# Sheet1.net
KiCad netlist of a schematic drawn in Altium Designer
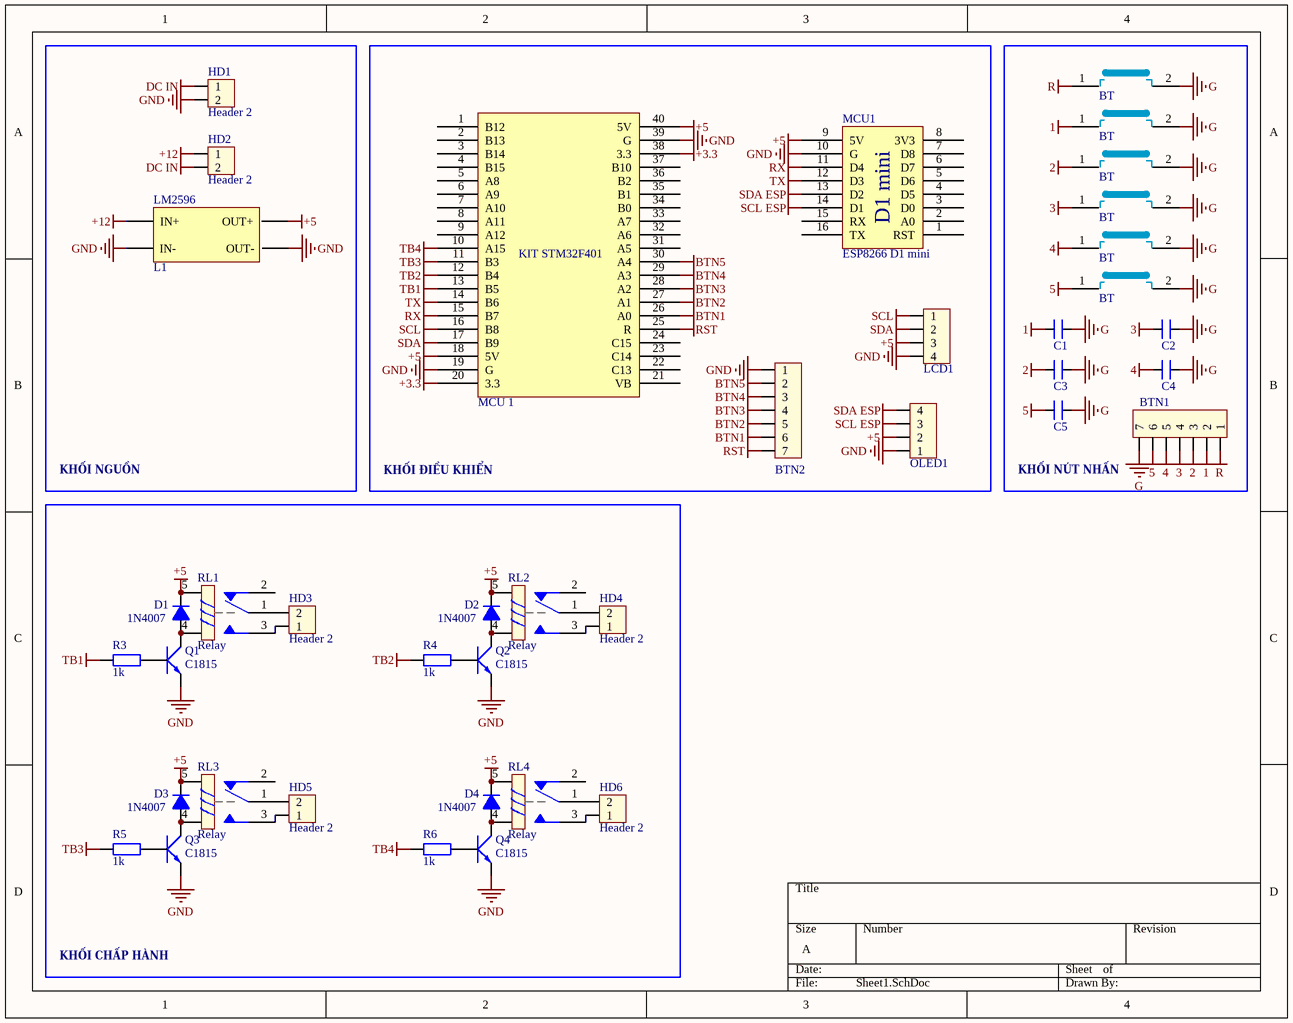
[diagram p0: Sheet1.SchDoc]

(export (version "E")
  (design (tool "Eeschema 10.0.6"))
  (components
    (comp (ref "BT1") (value "BT") (footprint "SW4") (libsource (lib "MY_LIBRARY") (part "BUTTON")))
    (comp (ref "BT2") (value "BT") (footprint "SW4") (libsource (lib "MY_LIBRARY") (part "BUTTON")))
    (comp (ref "BT3") (value "BT") (footprint "SW4") (libsource (lib "MY_LIBRARY") (part "BUTTON")))
    (comp (ref "BT4") (value "BT") (footprint "SW4") (libsource (lib "MY_LIBRARY") (part "BUTTON")))
    (comp (ref "BT5") (value "BT") (footprint "SW4") (libsource (lib "MY_LIBRARY") (part "BUTTON")))
    (comp (ref "BT6") (value "BT") (footprint "SW4") (libsource (lib "MY_LIBRARY") (part "BUTTON")))
    (comp (ref "BTN1")
      (value "JP7")
      (footprint "CON7")
      (description "Connector 7")
      (libsource (lib "MY_LIBRARY") (part "Con7"))
    )
    (comp (ref "BTN2")
      (value "JP7")
      (footprint "CON7")
      (description "Connector 7")
      (libsource (lib "MY_LIBRARY") (part "Con7"))
    )
    (comp (ref "C1") (value "CAP gom") (footprint "CN1") (libsource (lib "MY_LIBRARY") (part "CAP gom")))
    (comp (ref "C2") (value "CAP gom") (footprint "CN1") (libsource (lib "MY_LIBRARY") (part "CAP gom")))
    (comp (ref "C3") (value "CAP gom") (footprint "CN1") (libsource (lib "MY_LIBRARY") (part "CAP gom")))
    (comp (ref "C4") (value "CAP gom") (footprint "CN1") (libsource (lib "MY_LIBRARY") (part "CAP gom")))
    (comp (ref "C5") (value "CAP gom") (footprint "CN1") (libsource (lib "MY_LIBRARY") (part "CAP gom")))
    (comp (ref "D1")
      (value "1N4007")
      (footprint "D2A")
      (description "Diode 1A")
      (libsource (lib "Thuvien3D") (part "D1A"))
    )
    (comp (ref "D2")
      (value "1N4007")
      (footprint "D2A")
      (description "Diode 1A")
      (libsource (lib "Thuvien3D") (part "D1A"))
    )
    (comp (ref "D3")
      (value "1N4007")
      (footprint "D2A")
      (description "Diode 1A")
      (libsource (lib "Thuvien3D") (part "D1A"))
    )
    (comp (ref "D4")
      (value "1N4007")
      (footprint "D2A")
      (description "Diode 1A")
      (libsource (lib "Thuvien3D") (part "D1A"))
    )
    (comp (ref "HD1")
      (value "Header 2")
      (footprint "HED2")
      (description "Header 2 (Green)")
      (libsource (lib "Thuvien3D") (part "Hed2"))
    )
    (comp (ref "HD2")
      (value "Header 2")
      (footprint "HED2")
      (description "Header 2 (Green)")
      (libsource (lib "Thuvien3D") (part "Hed2"))
    )
    (comp (ref "HD3")
      (value "Header 2")
      (footprint "HED2")
      (description "Header 2 (Green)")
      (libsource (lib "") (part "Hed2_1"))
    )
    (comp (ref "HD4")
      (value "Header 2")
      (footprint "HED2")
      (description "Header 2 (Green)")
      (libsource (lib "") (part "Hed2_1"))
    )
    (comp (ref "HD5")
      (value "Header 2")
      (footprint "HED2")
      (description "Header 2 (Green)")
      (libsource (lib "") (part "Hed2_1"))
    )
    (comp (ref "HD6")
      (value "Header 2")
      (footprint "HED2")
      (description "Header 2 (Green)")
      (libsource (lib "") (part "Hed2_1"))
    )
    (comp (ref "L1")
      (value "BUCK_LM2596")
      (footprint "BUCK_LM2596")
      (libsource (lib "MY_LIBRARY") (part "BUCK_LM2596"))
    )
    (comp (ref "LCD1")
      (value "JP4")
      (footprint "CON4")
      (description "Connector 4")
      (libsource (lib "") (part "Con4_1"))
    )
    (comp (ref "MCU 1")
      (value "KIT STM32F401")
      (footprint "KIT STM32F401")
      (libsource (lib "MY_LIBRARY") (part "KIT STM32F401"))
    )
    (comp (ref "MCU1")
      (value "ESP8266 D1 mini")
      (footprint "ESP D1 mini")
      (libsource (lib "MY_LIBRARY") (part "ESP8266 D1 mini"))
    )
    (comp (ref "OLED1")
      (value "JP4")
      (footprint "CON4")
      (description "Connector 4")
      (libsource (lib "MY_LIBRARY") (part "Con4"))
    )
    (comp (ref "Q1")
      (value "C1815")
      (footprint "QTO-92")
      (description "NPN 600mW, ECB")
      (libsource (lib "Thuvien3D") (part "C1815"))
    )
    (comp (ref "Q2")
      (value "C1815")
      (footprint "QTO-92")
      (description "NPN 600mW, ECB")
      (libsource (lib "Thuvien3D") (part "C1815"))
    )
    (comp (ref "Q3")
      (value "C1815")
      (footprint "QTO-92")
      (description "NPN 600mW, ECB")
      (libsource (lib "Thuvien3D") (part "C1815"))
    )
    (comp (ref "Q4")
      (value "C1815")
      (footprint "QTO-92")
      (description "NPN 600mW, ECB")
      (libsource (lib "Thuvien3D") (part "C1815"))
    )
    (comp (ref "R3")
      (value "1k")
      (footprint "R1/2W")
      (description "Resistor 1/4W")
      (libsource (lib "Thuvien3D") (part "R1/4W"))
    )
    (comp (ref "R4")
      (value "1k")
      (footprint "R1/2W")
      (description "Resistor 1/4W")
      (libsource (lib "Thuvien3D") (part "R1/4W"))
    )
    (comp (ref "R5")
      (value "1k")
      (footprint "R1/2W")
      (description "Resistor 1/4W")
      (libsource (lib "Thuvien3D") (part "R1/4W"))
    )
    (comp (ref "R6")
      (value "1k")
      (footprint "R1/2W")
      (description "Resistor 1/4W")
      (libsource (lib "Thuvien3D") (part "R1/4W"))
    )
    (comp (ref "RL1")
      (value "Relay")
      (footprint "RL_SPDT_10A")
      (description "Relay SPDT 5 Pin")
      (libsource (lib "MY_LIBRARY") (part "Relay SRD"))
    )
    (comp (ref "RL2")
      (value "Relay")
      (footprint "RL_SPDT_10A")
      (description "Relay SPDT 5 Pin")
      (libsource (lib "MY_LIBRARY") (part "Relay SRD"))
    )
    (comp (ref "RL3")
      (value "Relay")
      (footprint "RL_SPDT_10A")
      (description "Relay SPDT 5 Pin")
      (libsource (lib "MY_LIBRARY") (part "Relay SRD"))
    )
    (comp (ref "RL4")
      (value "Relay")
      (footprint "RL_SPDT_10A")
      (description "Relay SPDT 5 Pin")
      (libsource (lib "MY_LIBRARY") (part "Relay SRD"))
    )
  )
  (nets
    (net (code "1") (name "+3.3") (class "Default")
      (node (ref "MCU 1") (pin "20") (pinfunction "3.3_20") (pintype "passive"))
      (node (ref "MCU 1") (pin "38") (pinfunction "3.3_38") (pintype "passive"))
    )
    (net (code "2") (name "+5") (class "Default")
      (node (ref "D1") (pin "2") (pinfunction "K_2") (pintype "passive"))
      (node (ref "D2") (pin "2") (pinfunction "K_2") (pintype "passive"))
      (node (ref "D3") (pin "2") (pinfunction "K_2") (pintype "passive"))
      (node (ref "D4") (pin "2") (pinfunction "K_2") (pintype "passive"))
      (node (ref "L1") (pin "4") (pinfunction "OUT+_4") (pintype "passive"))
      (node (ref "LCD1") (pin "3") (pinfunction "3_3") (pintype "passive"))
      (node (ref "MCU 1") (pin "18") (pinfunction "5V_18") (pintype "passive"))
      (node (ref "MCU 1") (pin "40") (pinfunction "5V_40") (pintype "passive"))
      (node (ref "MCU1") (pin "9") (pinfunction "5V_9") (pintype "passive"))
      (node (ref "OLED1") (pin "2") (pinfunction "2_2") (pintype "passive"))
      (node (ref "RL1") (pin "5") (pinfunction "5_5") (pintype "passive"))
      (node (ref "RL2") (pin "5") (pinfunction "5_5") (pintype "passive"))
      (node (ref "RL3") (pin "5") (pinfunction "5_5") (pintype "passive"))
      (node (ref "RL4") (pin "5") (pinfunction "5_5") (pintype "passive"))
    )
    (net (code "3") (name "+12") (class "Default")
      (node (ref "HD2") (pin "1") (pinfunction "1_1") (pintype "passive"))
      (node (ref "L1") (pin "1") (pinfunction "IN+_1") (pintype "passive"))
    )
    (net (code "4") (name "1") (class "Default")
      (node (ref "BT2") (pin "1") (pinfunction "1_1") (pintype "passive"))
      (node (ref "BTN1") (pin "2") (pinfunction "2_2") (pintype "passive"))
      (node (ref "C1") (pin "2") (pinfunction "2_2") (pintype "passive"))
    )
    (net (code "5") (name "2") (class "Default")
      (node (ref "BT3") (pin "1") (pinfunction "1_1") (pintype "passive"))
      (node (ref "BTN1") (pin "3") (pinfunction "3_3") (pintype "passive"))
      (node (ref "C3") (pin "2") (pinfunction "2_2") (pintype "passive"))
    )
    (net (code "6") (name "3") (class "Default")
      (node (ref "BT4") (pin "1") (pinfunction "1_1") (pintype "passive"))
      (node (ref "BTN1") (pin "4") (pinfunction "4_4") (pintype "passive"))
      (node (ref "C2") (pin "2") (pinfunction "2_2") (pintype "passive"))
    )
    (net (code "7") (name "4") (class "Default")
      (node (ref "BT5") (pin "1") (pinfunction "1_1") (pintype "passive"))
      (node (ref "BTN1") (pin "5") (pinfunction "5_5") (pintype "passive"))
      (node (ref "C4") (pin "2") (pinfunction "2_2") (pintype "passive"))
    )
    (net (code "8") (name "5") (class "Default")
      (node (ref "BT6") (pin "1") (pinfunction "1_1") (pintype "passive"))
      (node (ref "BTN1") (pin "6") (pinfunction "6_6") (pintype "passive"))
      (node (ref "C5") (pin "2") (pinfunction "2_2") (pintype "passive"))
    )
    (net (code "9") (name "BTN1") (class "Default")
      (node (ref "BTN2") (pin "6") (pinfunction "6_6") (pintype "passive"))
      (node (ref "MCU 1") (pin "26") (pinfunction "A0_26") (pintype "passive"))
    )
    (net (code "10") (name "BTN2") (class "Default")
      (node (ref "BTN2") (pin "5") (pinfunction "5_5") (pintype "passive"))
      (node (ref "MCU 1") (pin "27") (pinfunction "A1_27") (pintype "passive"))
    )
    (net (code "11") (name "BTN3") (class "Default")
      (node (ref "BTN2") (pin "4") (pinfunction "4_4") (pintype "passive"))
      (node (ref "MCU 1") (pin "28") (pinfunction "A2_28") (pintype "passive"))
    )
    (net (code "12") (name "BTN4") (class "Default")
      (node (ref "BTN2") (pin "3") (pinfunction "3_3") (pintype "passive"))
      (node (ref "MCU 1") (pin "29") (pinfunction "A3_29") (pintype "passive"))
    )
    (net (code "13") (name "BTN5") (class "Default")
      (node (ref "BTN2") (pin "2") (pinfunction "2_2") (pintype "passive"))
      (node (ref "MCU 1") (pin "30") (pinfunction "A4_30") (pintype "passive"))
    )
    (net (code "14") (name "DC IN") (class "Default")
      (node (ref "HD1") (pin "1") (pinfunction "1_1") (pintype "passive"))
      (node (ref "HD2") (pin "2") (pinfunction "2_2") (pintype "passive"))
    )
    (net (code "15") (name "G") (class "Default")
      (node (ref "BT1") (pin "2") (pinfunction "2_2") (pintype "passive"))
      (node (ref "BT2") (pin "2") (pinfunction "2_2") (pintype "passive"))
      (node (ref "BT3") (pin "2") (pinfunction "2_2") (pintype "passive"))
      (node (ref "BT4") (pin "2") (pinfunction "2_2") (pintype "passive"))
      (node (ref "BT5") (pin "2") (pinfunction "2_2") (pintype "passive"))
      (node (ref "BT6") (pin "2") (pinfunction "2_2") (pintype "passive"))
      (node (ref "BTN1") (pin "7") (pinfunction "7_7") (pintype "passive"))
      (node (ref "C1") (pin "1") (pinfunction "1_1") (pintype "passive"))
      (node (ref "C2") (pin "1") (pinfunction "1_1") (pintype "passive"))
      (node (ref "C3") (pin "1") (pinfunction "1_1") (pintype "passive"))
      (node (ref "C4") (pin "1") (pinfunction "1_1") (pintype "passive"))
      (node (ref "C5") (pin "1") (pinfunction "1_1") (pintype "passive"))
    )
    (net (code "16") (name "GND") (class "Default")
      (node (ref "BTN2") (pin "1") (pinfunction "1_1") (pintype "passive"))
      (node (ref "HD1") (pin "2") (pinfunction "2_2") (pintype "passive"))
      (node (ref "L1") (pin "2") (pinfunction "IN-_2") (pintype "passive"))
      (node (ref "L1") (pin "3") (pinfunction "OUT-_3") (pintype "passive"))
      (node (ref "LCD1") (pin "4") (pinfunction "4_4") (pintype "passive"))
      (node (ref "MCU 1") (pin "19") (pinfunction "G_19") (pintype "passive"))
      (node (ref "MCU 1") (pin "39") (pinfunction "G_39") (pintype "passive"))
      (node (ref "MCU1") (pin "10") (pinfunction "G_10") (pintype "passive"))
      (node (ref "OLED1") (pin "1") (pinfunction "1_1") (pintype "passive"))
      (node (ref "Q1") (pin "1") (pinfunction "E_1") (pintype "passive"))
      (node (ref "Q2") (pin "1") (pinfunction "E_1") (pintype "passive"))
      (node (ref "Q3") (pin "1") (pinfunction "E_1") (pintype "passive"))
      (node (ref "Q4") (pin "1") (pinfunction "E_1") (pintype "passive"))
    )
    (net (code "17") (name "Net-(D1-A)") (class "Default")
      (node (ref "D1") (pin "1") (pinfunction "A_1") (pintype "passive"))
      (node (ref "Q1") (pin "2") (pinfunction "C_2") (pintype "passive"))
      (node (ref "RL1") (pin "4") (pinfunction "4_4") (pintype "passive"))
    )
    (net (code "18") (name "Net-(D2-A)") (class "Default")
      (node (ref "D2") (pin "1") (pinfunction "A_1") (pintype "passive"))
      (node (ref "Q2") (pin "2") (pinfunction "C_2") (pintype "passive"))
      (node (ref "RL2") (pin "4") (pinfunction "4_4") (pintype "passive"))
    )
    (net (code "19") (name "Net-(D3-A)") (class "Default")
      (node (ref "D3") (pin "1") (pinfunction "A_1") (pintype "passive"))
      (node (ref "Q3") (pin "2") (pinfunction "C_2") (pintype "passive"))
      (node (ref "RL3") (pin "4") (pinfunction "4_4") (pintype "passive"))
    )
    (net (code "20") (name "Net-(D4-A)") (class "Default")
      (node (ref "D4") (pin "1") (pinfunction "A_1") (pintype "passive"))
      (node (ref "Q4") (pin "2") (pinfunction "C_2") (pintype "passive"))
      (node (ref "RL4") (pin "4") (pinfunction "4_4") (pintype "passive"))
    )
    (net (code "21") (name "Net-(HD3-Pad1)") (class "Default")
      (node (ref "HD3") (pin "1") (pinfunction "1_1") (pintype "passive"))
      (node (ref "RL1") (pin "3") (pinfunction "3_3") (pintype "passive"))
    )
    (net (code "22") (name "Net-(HD3-Pad2)") (class "Default")
      (node (ref "HD3") (pin "2") (pinfunction "2_2") (pintype "passive"))
      (node (ref "RL1") (pin "1") (pinfunction "1_1") (pintype "passive"))
    )
    (net (code "23") (name "Net-(HD4-Pad1)") (class "Default")
      (node (ref "HD4") (pin "1") (pinfunction "1_1") (pintype "passive"))
      (node (ref "RL2") (pin "3") (pinfunction "3_3") (pintype "passive"))
    )
    (net (code "24") (name "Net-(HD4-Pad2)") (class "Default")
      (node (ref "HD4") (pin "2") (pinfunction "2_2") (pintype "passive"))
      (node (ref "RL2") (pin "1") (pinfunction "1_1") (pintype "passive"))
    )
    (net (code "25") (name "Net-(HD5-Pad1)") (class "Default")
      (node (ref "HD5") (pin "1") (pinfunction "1_1") (pintype "passive"))
      (node (ref "RL3") (pin "3") (pinfunction "3_3") (pintype "passive"))
    )
    (net (code "26") (name "Net-(HD5-Pad2)") (class "Default")
      (node (ref "HD5") (pin "2") (pinfunction "2_2") (pintype "passive"))
      (node (ref "RL3") (pin "1") (pinfunction "1_1") (pintype "passive"))
    )
    (net (code "27") (name "Net-(HD6-Pad1)") (class "Default")
      (node (ref "HD6") (pin "1") (pinfunction "1_1") (pintype "passive"))
      (node (ref "RL4") (pin "3") (pinfunction "3_3") (pintype "passive"))
    )
    (net (code "28") (name "Net-(HD6-Pad2)") (class "Default")
      (node (ref "HD6") (pin "2") (pinfunction "2_2") (pintype "passive"))
      (node (ref "RL4") (pin "1") (pinfunction "1_1") (pintype "passive"))
    )
    (net (code "29") (name "Net-(Q1-B)") (class "Default")
      (node (ref "Q1") (pin "3") (pinfunction "B_3") (pintype "passive"))
      (node (ref "R3") (pin "1") (pinfunction "1_1") (pintype "passive"))
    )
    (net (code "30") (name "Net-(Q2-B)") (class "Default")
      (node (ref "Q2") (pin "3") (pinfunction "B_3") (pintype "passive"))
      (node (ref "R4") (pin "1") (pinfunction "1_1") (pintype "passive"))
    )
    (net (code "31") (name "Net-(Q3-B)") (class "Default")
      (node (ref "Q3") (pin "3") (pinfunction "B_3") (pintype "passive"))
      (node (ref "R5") (pin "1") (pinfunction "1_1") (pintype "passive"))
    )
    (net (code "32") (name "Net-(Q4-B)") (class "Default")
      (node (ref "Q4") (pin "3") (pinfunction "B_3") (pintype "passive"))
      (node (ref "R6") (pin "1") (pinfunction "1_1") (pintype "passive"))
    )
    (net (code "33") (name "R") (class "Default")
      (node (ref "BT1") (pin "1") (pinfunction "1_1") (pintype "passive"))
      (node (ref "BTN1") (pin "1") (pinfunction "1_1") (pintype "passive"))
    )
    (net (code "34") (name "RST") (class "Default")
      (node (ref "BTN2") (pin "7") (pinfunction "7_7") (pintype "passive"))
      (node (ref "MCU 1") (pin "25") (pinfunction "R_25") (pintype "passive"))
    )
    (net (code "35") (name "RX") (class "Default")
      (node (ref "MCU 1") (pin "15") (pinfunction "B7_15") (pintype "passive"))
      (node (ref "MCU1") (pin "11") (pinfunction "D4_11") (pintype "passive"))
    )
    (net (code "36") (name "SCL") (class "Default")
      (node (ref "LCD1") (pin "1") (pinfunction "1_1") (pintype "passive"))
      (node (ref "MCU 1") (pin "16") (pinfunction "B8_16") (pintype "passive"))
    )
    (net (code "37") (name "SCL ESP") (class "Default")
      (node (ref "MCU1") (pin "14") (pinfunction "D1_14") (pintype "passive"))
      (node (ref "OLED1") (pin "3") (pinfunction "3_3") (pintype "passive"))
    )
    (net (code "38") (name "SDA") (class "Default")
      (node (ref "LCD1") (pin "2") (pinfunction "2_2") (pintype "passive"))
      (node (ref "MCU 1") (pin "17") (pinfunction "B9_17") (pintype "passive"))
    )
    (net (code "39") (name "SDA ESP") (class "Default")
      (node (ref "MCU1") (pin "13") (pinfunction "D2_13") (pintype "passive"))
      (node (ref "OLED1") (pin "4") (pinfunction "4_4") (pintype "passive"))
    )
    (net (code "40") (name "TB1") (class "Default")
      (node (ref "MCU 1") (pin "13") (pinfunction "B5_13") (pintype "passive"))
      (node (ref "R3") (pin "2") (pinfunction "2_2") (pintype "passive"))
    )
    (net (code "41") (name "TB2") (class "Default")
      (node (ref "MCU 1") (pin "12") (pinfunction "B4_12") (pintype "passive"))
      (node (ref "R4") (pin "2") (pinfunction "2_2") (pintype "passive"))
    )
    (net (code "42") (name "TB3") (class "Default")
      (node (ref "MCU 1") (pin "11") (pinfunction "B3_11") (pintype "passive"))
      (node (ref "R5") (pin "2") (pinfunction "2_2") (pintype "passive"))
    )
    (net (code "43") (name "TB4") (class "Default")
      (node (ref "MCU 1") (pin "10") (pinfunction "A15_10") (pintype "passive"))
      (node (ref "R6") (pin "2") (pinfunction "2_2") (pintype "passive"))
    )
    (net (code "44") (name "TX") (class "Default")
      (node (ref "MCU 1") (pin "14") (pinfunction "B6_14") (pintype "passive"))
      (node (ref "MCU1") (pin "12") (pinfunction "D3_12") (pintype "passive"))
    )
    (net (code "45") (name "unconnected-(MCU 1-A5-Pad31)") (class "Default")
      (node (ref "MCU 1") (pin "31") (pinfunction "A5_31") (pintype "passive"))
    )
    (net (code "46") (name "unconnected-(MCU 1-A6-Pad32)") (class "Default")
      (node (ref "MCU 1") (pin "32") (pinfunction "A6_32") (pintype "passive"))
    )
    (net (code "47") (name "unconnected-(MCU 1-A7-Pad33)") (class "Default")
      (node (ref "MCU 1") (pin "33") (pinfunction "A7_33") (pintype "passive"))
    )
    (net (code "48") (name "unconnected-(MCU 1-A8-Pad5)") (class "Default")
      (node (ref "MCU 1") (pin "5") (pinfunction "A8_5") (pintype "passive"))
    )
    (net (code "49") (name "unconnected-(MCU 1-A9-Pad6)") (class "Default")
      (node (ref "MCU 1") (pin "6") (pinfunction "A9_6") (pintype "passive"))
    )
    (net (code "50") (name "unconnected-(MCU 1-A10-Pad7)") (class "Default")
      (node (ref "MCU 1") (pin "7") (pinfunction "A10_7") (pintype "passive"))
    )
    (net (code "51") (name "unconnected-(MCU 1-A11-Pad8)") (class "Default")
      (node (ref "MCU 1") (pin "8") (pinfunction "A11_8") (pintype "passive"))
    )
    (net (code "52") (name "unconnected-(MCU 1-A12-Pad9)") (class "Default")
      (node (ref "MCU 1") (pin "9") (pinfunction "A12_9") (pintype "passive"))
    )
    (net (code "53") (name "unconnected-(MCU 1-B0-Pad34)") (class "Default")
      (node (ref "MCU 1") (pin "34") (pinfunction "B0_34") (pintype "passive"))
    )
    (net (code "54") (name "unconnected-(MCU 1-B1-Pad35)") (class "Default")
      (node (ref "MCU 1") (pin "35") (pinfunction "B1_35") (pintype "passive"))
    )
    (net (code "55") (name "unconnected-(MCU 1-B2-Pad36)") (class "Default")
      (node (ref "MCU 1") (pin "36") (pinfunction "B2_36") (pintype "passive"))
    )
    (net (code "56") (name "unconnected-(MCU 1-B10-Pad37)") (class "Default")
      (node (ref "MCU 1") (pin "37") (pinfunction "B10_37") (pintype "passive"))
    )
    (net (code "57") (name "unconnected-(MCU 1-B12-Pad1)") (class "Default")
      (node (ref "MCU 1") (pin "1") (pinfunction "B12_1") (pintype "passive"))
    )
    (net (code "58") (name "unconnected-(MCU 1-B13-Pad2)") (class "Default")
      (node (ref "MCU 1") (pin "2") (pinfunction "B13_2") (pintype "passive"))
    )
    (net (code "59") (name "unconnected-(MCU 1-B14-Pad3)") (class "Default")
      (node (ref "MCU 1") (pin "3") (pinfunction "B14_3") (pintype "passive"))
    )
    (net (code "60") (name "unconnected-(MCU 1-B15-Pad4)") (class "Default")
      (node (ref "MCU 1") (pin "4") (pinfunction "B15_4") (pintype "passive"))
    )
    (net (code "61") (name "unconnected-(MCU 1-C13-Pad22)") (class "Default")
      (node (ref "MCU 1") (pin "22") (pinfunction "C13_22") (pintype "passive"))
    )
    (net (code "62") (name "unconnected-(MCU 1-C14-Pad23)") (class "Default")
      (node (ref "MCU 1") (pin "23") (pinfunction "C14_23") (pintype "passive"))
    )
    (net (code "63") (name "unconnected-(MCU 1-C15-Pad24)") (class "Default")
      (node (ref "MCU 1") (pin "24") (pinfunction "C15_24") (pintype "passive"))
    )
    (net (code "64") (name "unconnected-(MCU 1-VB-Pad21)") (class "Default")
      (node (ref "MCU 1") (pin "21") (pinfunction "VB_21") (pintype "passive"))
    )
    (net (code "65") (name "unconnected-(MCU1-3V3-Pad8)") (class "Default")
      (node (ref "MCU1") (pin "8") (pinfunction "3V3_8") (pintype "passive"))
    )
    (net (code "66") (name "unconnected-(MCU1-A0-Pad2)") (class "Default")
      (node (ref "MCU1") (pin "2") (pinfunction "A0_2") (pintype "passive"))
    )
    (net (code "67") (name "unconnected-(MCU1-D0-Pad3)") (class "Default")
      (node (ref "MCU1") (pin "3") (pinfunction "D0_3") (pintype "passive"))
    )
    (net (code "68") (name "unconnected-(MCU1-D5-Pad4)") (class "Default")
      (node (ref "MCU1") (pin "4") (pinfunction "D5_4") (pintype "passive"))
    )
    (net (code "69") (name "unconnected-(MCU1-D6-Pad5)") (class "Default")
      (node (ref "MCU1") (pin "5") (pinfunction "D6_5") (pintype "passive"))
    )
    (net (code "70") (name "unconnected-(MCU1-D7-Pad6)") (class "Default")
      (node (ref "MCU1") (pin "6") (pinfunction "D7_6") (pintype "passive"))
    )
    (net (code "71") (name "unconnected-(MCU1-D8-Pad7)") (class "Default")
      (node (ref "MCU1") (pin "7") (pinfunction "D8_7") (pintype "passive"))
    )
    (net (code "72") (name "unconnected-(MCU1-RST-Pad1)") (class "Default")
      (node (ref "MCU1") (pin "1") (pinfunction "RST_1") (pintype "passive"))
    )
    (net (code "73") (name "unconnected-(MCU1-RX-Pad15)") (class "Default")
      (node (ref "MCU1") (pin "15") (pinfunction "RX_15") (pintype "passive"))
    )
    (net (code "74") (name "unconnected-(MCU1-TX-Pad16)") (class "Default")
      (node (ref "MCU1") (pin "16") (pinfunction "TX_16") (pintype "passive"))
    )
    (net (code "75") (name "unconnected-(RL1-Pad2)") (class "Default")
      (node (ref "RL1") (pin "2") (pinfunction "2_2") (pintype "passive"))
    )
    (net (code "76") (name "unconnected-(RL2-Pad2)") (class "Default")
      (node (ref "RL2") (pin "2") (pinfunction "2_2") (pintype "passive"))
    )
    (net (code "77") (name "unconnected-(RL3-Pad2)") (class "Default")
      (node (ref "RL3") (pin "2") (pinfunction "2_2") (pintype "passive"))
    )
    (net (code "78") (name "unconnected-(RL4-Pad2)") (class "Default")
      (node (ref "RL4") (pin "2") (pinfunction "2_2") (pintype "passive"))
    )
  )
)
